# arduino_uno_to_atmega_328p.net
KiCad netlist of a schematic drawn in EAGLE
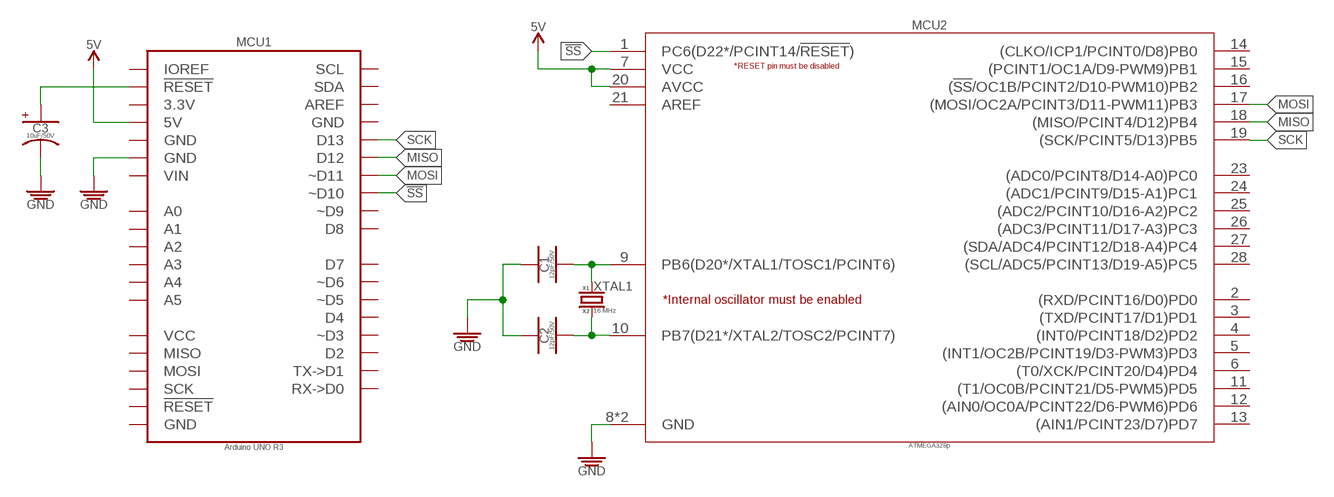
[diagram p0: schematic, sheet 1]

(export (version "E")
  (design (tool "Eeschema 10.0.6"))
  (components
    (comp (ref "C1")
      (value "12pF/50V")
      (footprint "eagle-import:_CER_PTH_LS2.5_L4-W2.5-H5.58")
      (fields (field (name "MFR") "Vishay BC Components") (field (name "MPN") "K120J15C0GF5TL2"))
      (libsource (lib "eagle-import") (part "12PF_PTH-CER_50V-5%"))
    )
    (comp (ref "C2")
      (value "12pF/50V")
      (footprint "eagle-import:_CER_PTH_LS2.5_L4-W2.5-H5.58")
      (fields (field (name "MFR") "Vishay BC Components") (field (name "MPN") "K120J15C0GF5TL2"))
      (libsource (lib "eagle-import") (part "12PF_PTH-CER_50V-5%"))
    )
    (comp (ref "C3")
      (value "10uF/50V")
      (footprint "eagle-import:_AE_PTH-DIA5-LS2-H5")
      (fields (field (name "MFR") "Panasonic Electronic Components") (field (name "MPN") "ECE-A1HKA100"))
      (libsource (lib "eagle-import") (part "10UF-POLARIZED_PTH_50V-20%"))
    )
    (comp (ref "MCU1")
      (value "Arduino UNO R3")
      (footprint "eagle-import:ARDUINO_UNO_R3")
      (fields (field (name "MFR") "Arduino") (field (name "MPN") "A000066"))
      (libsource (lib "eagle-import") (part "ARDUINO_UNO_R3"))
    )
    (comp (ref "MCU2")
      (value "ATMEGA328p")
      (footprint "eagle-import:DIP762W53P254L3467H472Q28B")
      (fields (field (name "MFR") "Microchip Technology") (field (name "MPN") "ATMEGA328P-PU"))
      (libsource (lib "eagle-import") (part "ATMEGA328P-28_28-PDIP_8BIT_32KB"))
    )
    (comp (ref "XTAL1")
      (value "16 MHz")
      (footprint "eagle-import:HC-49_US")
      (fields (field (name "MFR") "Abracon LLC") (field (name "MPN") "ABL-16.000MHZ-B2"))
      (libsource (lib "eagle-import") (part "CRYSTAL_ABL_16MHZ_18PF"))
    )
  )
  (nets
    (net (code "1") (name "/~{SS}") (class "Default")
      (node (ref "MCU1") (pin "D10") (pinfunction "~{D10}_D10") (pintype "bidirectional"))
      (node (ref "MCU2") (pin "1") (pinfunction "PC6(D22*/PCINT14/~{RESET})_1") (pintype "bidirectional"))
    )
    (net (code "2") (name "5V") (class "Default")
      (node (ref "MCU1") (pin "5V") (pinfunction "5V_5V") (pintype "bidirectional"))
      (node (ref "MCU2") (pin "20") (pinfunction "AVCC_20") (pintype "power_in"))
      (node (ref "MCU2") (pin "7") (pinfunction "VCC_7") (pintype "power_in"))
    )
    (net (code "3") (name "GND") (class "Default")
      (node (ref "C1") (pin "P$1") (pinfunction "1_P$1") (pintype "passive"))
      (node (ref "C2") (pin "P$1") (pinfunction "1_P$1") (pintype "passive"))
      (node (ref "C3") (pin "-") (pinfunction "K_-") (pintype "passive"))
      (node (ref "MCU1") (pin "GND@3") (pinfunction "GND_GND@3") (pintype "bidirectional"))
      (node (ref "MCU2") (pin "22") (pinfunction "GND_22") (pintype "power_in"))
      (node (ref "MCU2") (pin "8") (pinfunction "GND_8") (pintype "power_in"))
    )
    (net (code "4") (name "MISO") (class "Default")
      (node (ref "MCU1") (pin "D12") (pinfunction "D12_D12") (pintype "bidirectional"))
      (node (ref "MCU2") (pin "18") (pinfunction "(MISO/PCINT4/D12)PB4_18") (pintype "bidirectional"))
    )
    (net (code "5") (name "MOSI") (class "Default")
      (node (ref "MCU1") (pin "D11") (pinfunction "~{D11}_D11") (pintype "bidirectional"))
      (node (ref "MCU2") (pin "17") (pinfunction "(MOSI/OC2A/PCINT3/D11-PWM11)PB3_17") (pintype "bidirectional"))
    )
    (net (code "6") (name "Net-(C1-2)") (class "Default")
      (node (ref "C1") (pin "P$2") (pinfunction "2_P$2") (pintype "passive"))
      (node (ref "MCU2") (pin "9") (pinfunction "PB6(D20*/XTAL1/TOSC1/PCINT6)_9") (pintype "bidirectional"))
      (node (ref "XTAL1") (pin "P$1") (pinfunction "XTAL1_P$1") (pintype "passive"))
    )
    (net (code "7") (name "Net-(C2-2)") (class "Default")
      (node (ref "C2") (pin "P$2") (pinfunction "2_P$2") (pintype "passive"))
      (node (ref "MCU2") (pin "10") (pinfunction "PB7(D21*/XTAL2/TOSC2/PCINT7)_10") (pintype "bidirectional"))
      (node (ref "XTAL1") (pin "P$2") (pinfunction "XTAL2_P$2") (pintype "passive"))
    )
    (net (code "8") (name "Net-(C3-A)") (class "Default")
      (node (ref "C3") (pin "+") (pinfunction "A_+") (pintype "passive"))
      (node (ref "MCU1") (pin "RESET@1") (pinfunction "~{RESET}_RESET@1") (pintype "bidirectional"))
    )
    (net (code "9") (name "SCK") (class "Default")
      (node (ref "MCU1") (pin "D13") (pinfunction "D13_D13") (pintype "bidirectional"))
      (node (ref "MCU2") (pin "19") (pinfunction "(SCK/PCINT5/D13)PB5_19") (pintype "bidirectional"))
    )
    (net (code "10") (name "unconnected-(MCU1-GND-PadGND@1)") (class "Default")
      (node (ref "MCU1") (pin "GND@1") (pinfunction "GND_GND@1") (pintype "bidirectional"))
    )
    (net (code "11") (name "unconnected-(MCU1-GND-PadGND@2)") (class "Default")
      (node (ref "MCU1") (pin "GND@2") (pinfunction "GND_GND@2") (pintype "bidirectional"))
    )
    (net (code "12") (name "unconnected-(MCU1-GND-PadGND@4)") (class "Default")
      (node (ref "MCU1") (pin "GND@4") (pinfunction "GND_GND@4") (pintype "bidirectional"))
    )
    (net (code "13") (name "unconnected-(MCU1-Pad3.3V)") (class "Default")
      (node (ref "MCU1") (pin "3.3V") (pinfunction "3.3V_3.3V") (pintype "bidirectional"))
    )
    (net (code "14") (name "unconnected-(MCU1-PadA0)") (class "Default")
      (node (ref "MCU1") (pin "A0") (pinfunction "A0_A0") (pintype "bidirectional"))
    )
    (net (code "15") (name "unconnected-(MCU1-PadA1)") (class "Default")
      (node (ref "MCU1") (pin "A1") (pinfunction "A1_A1") (pintype "bidirectional"))
    )
    (net (code "16") (name "unconnected-(MCU1-PadA2)") (class "Default")
      (node (ref "MCU1") (pin "A2") (pinfunction "A2_A2") (pintype "bidirectional"))
    )
    (net (code "17") (name "unconnected-(MCU1-PadA3)") (class "Default")
      (node (ref "MCU1") (pin "A3") (pinfunction "A3_A3") (pintype "bidirectional"))
    )
    (net (code "18") (name "unconnected-(MCU1-PadA4)") (class "Default")
      (node (ref "MCU1") (pin "A4") (pinfunction "A4_A4") (pintype "bidirectional"))
    )
    (net (code "19") (name "unconnected-(MCU1-PadA5)") (class "Default")
      (node (ref "MCU1") (pin "A5") (pinfunction "A5_A5") (pintype "bidirectional"))
    )
    (net (code "20") (name "unconnected-(MCU1-PadAREF)") (class "Default")
      (node (ref "MCU1") (pin "AREF") (pinfunction "AREF_AREF") (pintype "bidirectional"))
    )
    (net (code "21") (name "unconnected-(MCU1-PadD2)") (class "Default")
      (node (ref "MCU1") (pin "D2") (pinfunction "D2_D2") (pintype "bidirectional"))
    )
    (net (code "22") (name "unconnected-(MCU1-PadD4)") (class "Default")
      (node (ref "MCU1") (pin "D4") (pinfunction "D4_D4") (pintype "bidirectional"))
    )
    (net (code "23") (name "unconnected-(MCU1-PadD7)") (class "Default")
      (node (ref "MCU1") (pin "D7") (pinfunction "D7_D7") (pintype "bidirectional"))
    )
    (net (code "24") (name "unconnected-(MCU1-PadD8)") (class "Default")
      (node (ref "MCU1") (pin "D8") (pinfunction "D8_D8") (pintype "bidirectional"))
    )
    (net (code "25") (name "unconnected-(MCU1-PadIOREF)") (class "Default")
      (node (ref "MCU1") (pin "IOREF") (pinfunction "IOREF_IOREF") (pintype "bidirectional"))
    )
    (net (code "26") (name "unconnected-(MCU1-PadMISO)") (class "Default")
      (node (ref "MCU1") (pin "MISO") (pinfunction "MISO_MISO") (pintype "bidirectional"))
    )
    (net (code "27") (name "unconnected-(MCU1-PadMOSI)") (class "Default")
      (node (ref "MCU1") (pin "MOSI") (pinfunction "MOSI_MOSI") (pintype "bidirectional"))
    )
    (net (code "28") (name "unconnected-(MCU1-PadSCK)") (class "Default")
      (node (ref "MCU1") (pin "SCK") (pinfunction "SCK_SCK") (pintype "bidirectional"))
    )
    (net (code "29") (name "unconnected-(MCU1-PadSCL)") (class "Default")
      (node (ref "MCU1") (pin "SCL") (pinfunction "SCL_SCL") (pintype "bidirectional"))
    )
    (net (code "30") (name "unconnected-(MCU1-PadSDA)") (class "Default")
      (node (ref "MCU1") (pin "SDA") (pinfunction "SDA_SDA") (pintype "bidirectional"))
    )
    (net (code "31") (name "unconnected-(MCU1-PadVCC)") (class "Default")
      (node (ref "MCU1") (pin "VCC") (pinfunction "VCC_VCC") (pintype "bidirectional"))
    )
    (net (code "32") (name "unconnected-(MCU1-PadVIN)") (class "Default")
      (node (ref "MCU1") (pin "VIN") (pinfunction "VIN_VIN") (pintype "bidirectional"))
    )
    (net (code "33") (name "unconnected-(MCU1-RX->D0-PadD0)") (class "Default")
      (node (ref "MCU1") (pin "D0") (pinfunction "RX->D0_D0") (pintype "bidirectional"))
    )
    (net (code "34") (name "unconnected-(MCU1-TX->D1-PadD1)") (class "Default")
      (node (ref "MCU1") (pin "D1") (pinfunction "TX->D1_D1") (pintype "bidirectional"))
    )
    (net (code "35") (name "unconnected-(MCU1-~{D3}-PadD3)") (class "Default")
      (node (ref "MCU1") (pin "D3") (pinfunction "~{D3}_D3") (pintype "bidirectional"))
    )
    (net (code "36") (name "unconnected-(MCU1-~{D5}-PadD5)") (class "Default")
      (node (ref "MCU1") (pin "D5") (pinfunction "~{D5}_D5") (pintype "bidirectional"))
    )
    (net (code "37") (name "unconnected-(MCU1-~{D6}-PadD6)") (class "Default")
      (node (ref "MCU1") (pin "D6") (pinfunction "~{D6}_D6") (pintype "bidirectional"))
    )
    (net (code "38") (name "unconnected-(MCU1-~{D9}-PadD9)") (class "Default")
      (node (ref "MCU1") (pin "D9") (pinfunction "~{D9}_D9") (pintype "bidirectional"))
    )
    (net (code "39") (name "unconnected-(MCU1-~{RESET}-PadRESET@2)") (class "Default")
      (node (ref "MCU1") (pin "RESET@2") (pinfunction "~{RESET}_RESET@2") (pintype "bidirectional"))
    )
    (net (code "40") (name "unconnected-(MCU2-(ADC0{slash}PCINT8{slash}D14-A0)PC0-Pad23)") (class "Default")
      (node (ref "MCU2") (pin "23") (pinfunction "(ADC0/PCINT8/D14-A0)PC0_23") (pintype "bidirectional"))
    )
    (net (code "41") (name "unconnected-(MCU2-(ADC1{slash}PCINT9{slash}D15-A1)PC1-Pad24)") (class "Default")
      (node (ref "MCU2") (pin "24") (pinfunction "(ADC1/PCINT9/D15-A1)PC1_24") (pintype "bidirectional"))
    )
    (net (code "42") (name "unconnected-(MCU2-(ADC2{slash}PCINT10{slash}D16-A2)PC2-Pad25)") (class "Default")
      (node (ref "MCU2") (pin "25") (pinfunction "(ADC2/PCINT10/D16-A2)PC2_25") (pintype "bidirectional"))
    )
    (net (code "43") (name "unconnected-(MCU2-(ADC3{slash}PCINT11{slash}D17-A3)PC3-Pad26)") (class "Default")
      (node (ref "MCU2") (pin "26") (pinfunction "(ADC3/PCINT11/D17-A3)PC3_26") (pintype "bidirectional"))
    )
    (net (code "44") (name "unconnected-(MCU2-(AIN0{slash}OC0A{slash}PCINT22{slash}D6-PWM6)PD6-Pad12)") (class "Default")
      (node (ref "MCU2") (pin "12") (pinfunction "(AIN0/OC0A/PCINT22/D6-PWM6)PD6_12") (pintype "bidirectional"))
    )
    (net (code "45") (name "unconnected-(MCU2-(AIN1{slash}PCINT23{slash}D7)PD7-Pad13)") (class "Default")
      (node (ref "MCU2") (pin "13") (pinfunction "(AIN1/PCINT23/D7)PD7_13") (pintype "bidirectional"))
    )
    (net (code "46") (name "unconnected-(MCU2-(CLKO{slash}ICP1{slash}PCINT0{slash}D8)PB0-Pad14)") (class "Default")
      (node (ref "MCU2") (pin "14") (pinfunction "(CLKO/ICP1/PCINT0/D8)PB0_14") (pintype "bidirectional"))
    )
    (net (code "47") (name "unconnected-(MCU2-(INT0{slash}PCINT18{slash}D2)PD2-Pad4)") (class "Default")
      (node (ref "MCU2") (pin "4") (pinfunction "(INT0/PCINT18/D2)PD2_4") (pintype "bidirectional"))
    )
    (net (code "48") (name "unconnected-(MCU2-(INT1{slash}OC2B{slash}PCINT19{slash}D3-PWM3)PD3-Pad5)") (class "Default")
      (node (ref "MCU2") (pin "5") (pinfunction "(INT1/OC2B/PCINT19/D3-PWM3)PD3_5") (pintype "bidirectional"))
    )
    (net (code "49") (name "unconnected-(MCU2-(PCINT1{slash}OC1A{slash}D9-PWM9)PB1-Pad15)") (class "Default")
      (node (ref "MCU2") (pin "15") (pinfunction "(PCINT1/OC1A/D9-PWM9)PB1_15") (pintype "bidirectional"))
    )
    (net (code "50") (name "unconnected-(MCU2-(RXD{slash}PCINT16{slash}D0)PD0-Pad2)") (class "Default")
      (node (ref "MCU2") (pin "2") (pinfunction "(RXD/PCINT16/D0)PD0_2") (pintype "bidirectional"))
    )
    (net (code "51") (name "unconnected-(MCU2-(SCL{slash}ADC5{slash}PCINT13{slash}D19-A5)PC5-Pad28)") (class "Default")
      (node (ref "MCU2") (pin "28") (pinfunction "(SCL/ADC5/PCINT13/D19-A5)PC5_28") (pintype "bidirectional"))
    )
    (net (code "52") (name "unconnected-(MCU2-(SDA{slash}ADC4{slash}PCINT12{slash}D18-A4)PC4-Pad27)") (class "Default")
      (node (ref "MCU2") (pin "27") (pinfunction "(SDA/ADC4/PCINT12/D18-A4)PC4_27") (pintype "bidirectional"))
    )
    (net (code "53") (name "unconnected-(MCU2-(T0{slash}XCK{slash}PCINT20{slash}D4)PD4-Pad6)") (class "Default")
      (node (ref "MCU2") (pin "6") (pinfunction "(T0/XCK/PCINT20/D4)PD4_6") (pintype "bidirectional"))
    )
    (net (code "54") (name "unconnected-(MCU2-(T1{slash}OC0B{slash}PCINT21{slash}D5-PWM5)PD5-Pad11)") (class "Default")
      (node (ref "MCU2") (pin "11") (pinfunction "(T1/OC0B/PCINT21/D5-PWM5)PD5_11") (pintype "bidirectional"))
    )
    (net (code "55") (name "unconnected-(MCU2-(TXD{slash}PCINT17{slash}D1)PD1-Pad3)") (class "Default")
      (node (ref "MCU2") (pin "3") (pinfunction "(TXD/PCINT17/D1)PD1_3") (pintype "bidirectional"))
    )
    (net (code "56") (name "unconnected-(MCU2-(~{SS}{slash}OC1B{slash}PCINT2{slash}D10-PWM10)PB2-Pad16)") (class "Default")
      (node (ref "MCU2") (pin "16") (pinfunction "(~{SS}/OC1B/PCINT2/D10-PWM10)PB2_16") (pintype "bidirectional"))
    )
    (net (code "57") (name "unconnected-(MCU2-AREF-Pad21)") (class "Default")
      (node (ref "MCU2") (pin "21") (pinfunction "AREF_21") (pintype "passive"))
    )
  )
)
